# Y-babies_ATtiny84_v03.net
KiCad netlist of a schematic drawn in EAGLE
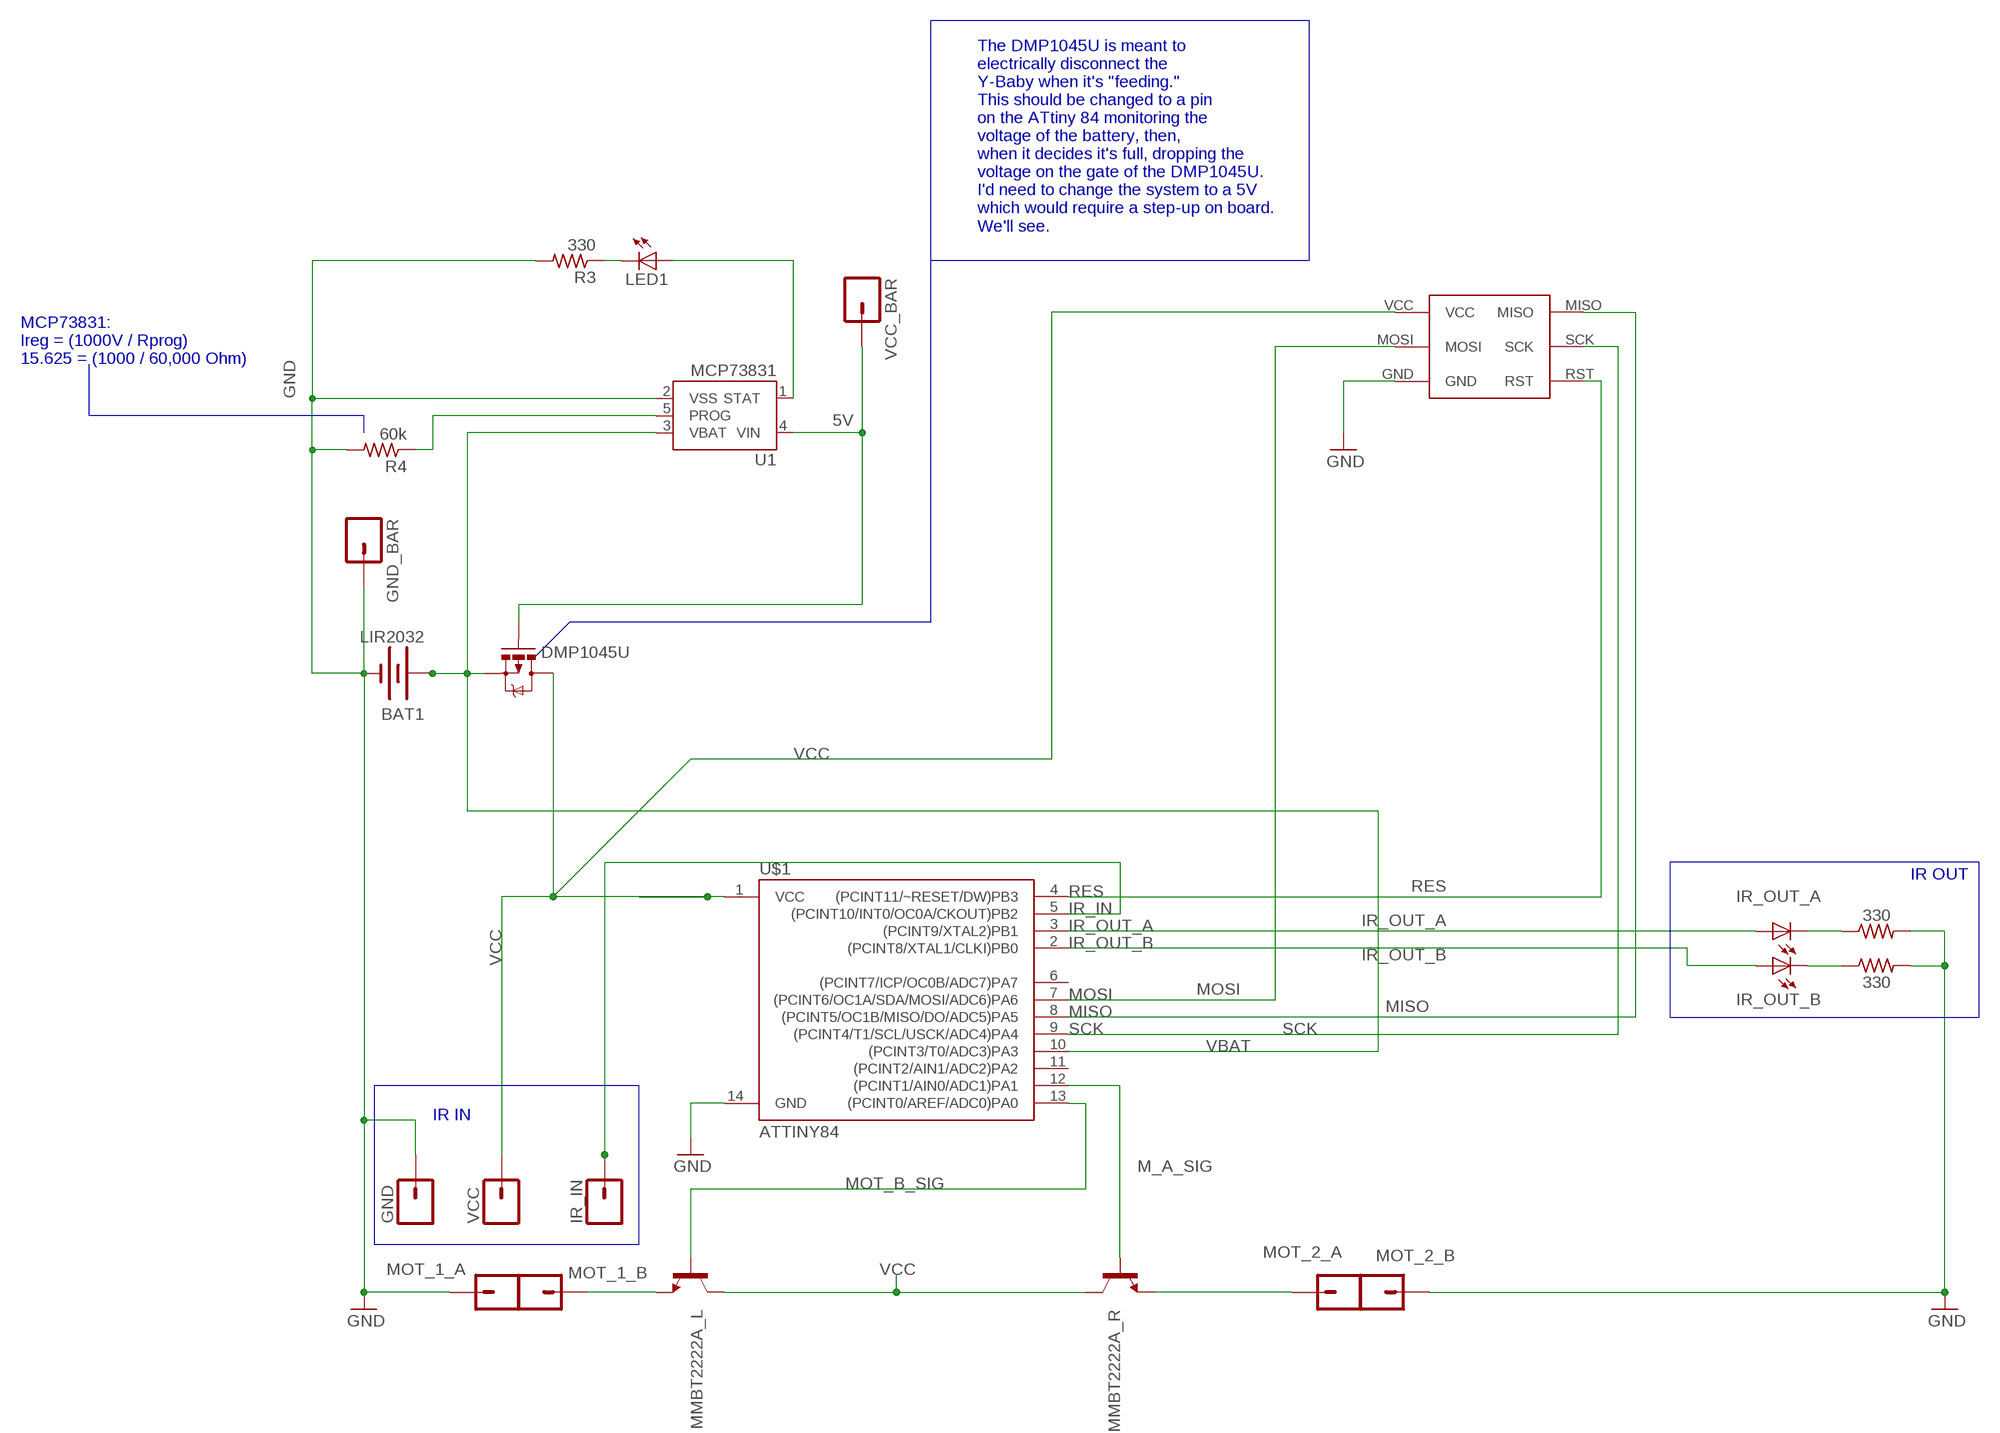
[diagram p0: schematic, sheet 1]

(export (version "E")
  (design (tool "Eeschema 10.0.6"))
  (components
    (comp (ref "BAT1")
      (value "LIR2032")
      (footprint "eagle-import:BATTCOM_20MM_PTH")
      (libsource (lib "eagle-import") (part "BATTERY20PTH"))
    )
    (comp (ref "DMP1045U")
      (value "MOSFET-PCHANNELSMD")
      (footprint "eagle-import:SOT23-3")
      (libsource (lib "eagle-import") (part "MOSFET-PCHANNELSMD"))
    )
    (comp (ref "GND")
      (value "M01PTH")
      (footprint "eagle-import:1X01")
      (libsource (lib "eagle-import") (part "M01PTH"))
    )
    (comp (ref "GND_BAR")
      (value "M01PTH")
      (footprint "eagle-import:1X01")
      (libsource (lib "eagle-import") (part "M01PTH"))
    )
    (comp (ref "IR_IN")
      (value "M01PTH")
      (footprint "eagle-import:1X01")
      (libsource (lib "eagle-import") (part "M01PTH"))
    )
    (comp (ref "IR_OUT_A")
      (value "LED3MM")
      (footprint "eagle-import:LED3MM")
      (libsource (lib "eagle-import") (part "LED3MM"))
    )
    (comp (ref "IR_OUT_B")
      (value "LED3MM")
      (footprint "eagle-import:LED3MM")
      (libsource (lib "eagle-import") (part "LED3MM"))
    )
    (comp (ref "LED1")
      (value "LEDSML0603")
      (footprint "eagle-import:SML0603")
      (libsource (lib "eagle-import") (part "LEDSML0603"))
    )
    (comp (ref "MMBT2222A_L")
      (value "TRANSISTOR_NPNSOT23")
      (footprint "eagle-import:SOT23")
      (libsource (lib "eagle-import") (part "TRANSISTOR_NPNSOT23"))
    )
    (comp (ref "MMBT2222A_R")
      (value "TRANSISTOR_NPNSOT23")
      (footprint "eagle-import:SOT23")
      (libsource (lib "eagle-import") (part "TRANSISTOR_NPNSOT23"))
    )
    (comp (ref "MOT_1_A")
      (value "M01SMD-4.5X1.5")
      (footprint "eagle-import:PAD-1.5X4.5")
      (libsource (lib "eagle-import") (part "M01SMD-4.5X1.5"))
    )
    (comp (ref "MOT_1_B")
      (value "M01SMD-4.5X1.5")
      (footprint "eagle-import:PAD-1.5X4.5")
      (libsource (lib "eagle-import") (part "M01SMD-4.5X1.5"))
    )
    (comp (ref "MOT_2_A")
      (value "M01SMD-4.5X1.5")
      (footprint "eagle-import:PAD-1.5X4.5")
      (libsource (lib "eagle-import") (part "M01SMD-4.5X1.5"))
    )
    (comp (ref "MOT_2_B")
      (value "M01SMD-4.5X1.5")
      (footprint "eagle-import:PAD-1.5X4.5")
      (libsource (lib "eagle-import") (part "M01SMD-4.5X1.5"))
    )
    (comp (ref "R1")
      (value "330")
      (footprint "eagle-import:R0402")
      (libsource (lib "eagle-import") (part "R-US_R0402"))
    )
    (comp (ref "R2")
      (value "330")
      (footprint "eagle-import:R0402")
      (libsource (lib "eagle-import") (part "R-US_R0402"))
    )
    (comp (ref "R3")
      (value "330")
      (footprint "eagle-import:R0402")
      (libsource (lib "eagle-import") (part "R-US_R0402"))
    )
    (comp (ref "R4")
      (value "60k")
      (footprint "eagle-import:R0402")
      (libsource (lib "eagle-import") (part "R-US_R0402"))
    )
    (comp (ref "U$1")
      (value "ATTINY84")
      (footprint "eagle-import:SO14")
      (libsource (lib "eagle-import") (part "ATTINY84"))
    )
    (comp (ref "U$2")
      (value "POGO_PIN_SPI_PAD")
      (footprint "eagle-import:POGO_PIN_SPI_PAD")
      (libsource (lib "eagle-import") (part "POGO_PIN_SPI_PAD"))
    )
    (comp (ref "U1")
      (value "MCP73831")
      (footprint "eagle-import:SOT23-5")
      (libsource (lib "eagle-import") (part "MCP73831"))
    )
    (comp (ref "VCC")
      (value "M01PTH")
      (footprint "eagle-import:1X01")
      (libsource (lib "eagle-import") (part "M01PTH"))
    )
    (comp (ref "VCC_BAR")
      (value "M01PTH")
      (footprint "eagle-import:1X01")
      (libsource (lib "eagle-import") (part "M01PTH"))
    )
  )
  (nets
    (net (code "1") (name "/5V") (class "Default")
      (node (ref "DMP1045U") (pin "1") (pinfunction "G_1") (pintype "passive"))
      (node (ref "U1") (pin "4") (pinfunction "VIN_4") (pintype "power_in"))
      (node (ref "VCC_BAR") (pin "1") (pinfunction "1_1") (pintype "passive"))
    )
    (net (code "2") (name "/IR_IN") (class "Default")
      (node (ref "IR_IN") (pin "1") (pinfunction "1_1") (pintype "passive"))
      (node (ref "U$1") (pin "5") (pinfunction "(PCINT10/INT0/OC0A/CKOUT)PB2_5") (pintype "bidirectional"))
    )
    (net (code "3") (name "/IR_OUT_A") (class "Default")
      (node (ref "IR_OUT_A") (pin "A") (pinfunction "A_A") (pintype "passive"))
      (node (ref "U$1") (pin "3") (pinfunction "(PCINT9/XTAL2)PB1_3") (pintype "bidirectional"))
    )
    (net (code "4") (name "/IR_OUT_B") (class "Default")
      (node (ref "IR_OUT_B") (pin "A") (pinfunction "A_A") (pintype "passive"))
      (node (ref "U$1") (pin "2") (pinfunction "(PCINT8/XTAL1/CLKI)PB0_2") (pintype "bidirectional"))
    )
    (net (code "5") (name "/MISO") (class "Default")
      (node (ref "U$1") (pin "8") (pinfunction "(PCINT5/OC1B/MISO/DO/ADC5)PA5_8") (pintype "bidirectional"))
      (node (ref "U$2") (pin "MISO") (pinfunction "MISO_MISO") (pintype "bidirectional"))
    )
    (net (code "6") (name "/MOSI") (class "Default")
      (node (ref "U$1") (pin "7") (pinfunction "(PCINT6/OC1A/SDA/MOSI/ADC6)PA6_7") (pintype "bidirectional"))
      (node (ref "U$2") (pin "MOSI") (pinfunction "MOSI_MOSI") (pintype "bidirectional"))
    )
    (net (code "7") (name "/MOT_B_SIG") (class "Default")
      (node (ref "MMBT2222A_L") (pin "1") (pinfunction "B_1") (pintype "passive"))
      (node (ref "U$1") (pin "13") (pinfunction "(PCINT0/AREF/ADC0)PA0_13") (pintype "bidirectional"))
    )
    (net (code "8") (name "/M_A_SIG") (class "Default")
      (node (ref "MMBT2222A_R") (pin "1") (pinfunction "B_1") (pintype "passive"))
      (node (ref "U$1") (pin "12") (pinfunction "(PCINT1/AIN0/ADC1)PA1_12") (pintype "bidirectional"))
    )
    (net (code "9") (name "/RES") (class "Default")
      (node (ref "U$1") (pin "4") (pinfunction "(PCINT11/~{RESET/DW})PB3_4") (pintype "bidirectional"))
      (node (ref "U$2") (pin "RST") (pinfunction "RST_RST") (pintype "bidirectional"))
    )
    (net (code "10") (name "/SCK") (class "Default")
      (node (ref "U$1") (pin "9") (pinfunction "(PCINT4/T1/SCL/USCK/ADC4)PA4_9") (pintype "bidirectional"))
      (node (ref "U$2") (pin "SCK") (pinfunction "SCK_SCK") (pintype "bidirectional"))
    )
    (net (code "11") (name "/VBAT") (class "Default")
      (node (ref "BAT1") (pin "1") (pinfunction "+_1") (pintype "power_in"))
      (node (ref "DMP1045U") (pin "2") (pinfunction "S_2") (pintype "passive"))
      (node (ref "U$1") (pin "10") (pinfunction "(PCINT3/T0/ADC3)PA3_10") (pintype "bidirectional"))
      (node (ref "U1") (pin "3") (pinfunction "VBAT_3") (pintype "power_in"))
    )
    (net (code "12") (name "/VCC") (class "Default")
      (node (ref "DMP1045U") (pin "3") (pinfunction "D_3") (pintype "passive"))
      (node (ref "MMBT2222A_L") (pin "3") (pinfunction "C_3") (pintype "passive"))
      (node (ref "MMBT2222A_R") (pin "3") (pinfunction "C_3") (pintype "passive"))
      (node (ref "U$1") (pin "1") (pinfunction "VCC_1") (pintype "bidirectional"))
      (node (ref "U$2") (pin "VCC") (pinfunction "VCC_VCC") (pintype "bidirectional"))
      (node (ref "VCC") (pin "1") (pinfunction "1_1") (pintype "passive"))
    )
    (net (code "13") (name "GND") (class "Default")
      (node (ref "BAT1") (pin "2") (pinfunction "-_2") (pintype "power_in"))
      (node (ref "GND") (pin "1") (pinfunction "1_1") (pintype "passive"))
      (node (ref "GND_BAR") (pin "1") (pinfunction "1_1") (pintype "passive"))
      (node (ref "MOT_1_A") (pin "P$1") (pinfunction "1_P$1") (pintype "passive"))
      (node (ref "MOT_2_B") (pin "P$1") (pinfunction "1_P$1") (pintype "passive"))
      (node (ref "R1") (pin "2") (pinfunction "2_2") (pintype "passive"))
      (node (ref "R2") (pin "2") (pinfunction "2_2") (pintype "passive"))
      (node (ref "R3") (pin "2") (pinfunction "2_2") (pintype "passive"))
      (node (ref "R4") (pin "2") (pinfunction "2_2") (pintype "passive"))
      (node (ref "U$1") (pin "14") (pinfunction "GND_14") (pintype "bidirectional"))
      (node (ref "U$2") (pin "GND") (pinfunction "GND_GND") (pintype "bidirectional"))
      (node (ref "U1") (pin "2") (pinfunction "VSS_2") (pintype "power_in"))
    )
    (net (code "14") (name "Net-(IR_OUT_A-C)") (class "Default")
      (node (ref "IR_OUT_A") (pin "K") (pinfunction "C_K") (pintype "passive"))
      (node (ref "R1") (pin "1") (pinfunction "1_1") (pintype "passive"))
    )
    (net (code "15") (name "Net-(IR_OUT_B-C)") (class "Default")
      (node (ref "IR_OUT_B") (pin "K") (pinfunction "C_K") (pintype "passive"))
      (node (ref "R2") (pin "1") (pinfunction "1_1") (pintype "passive"))
    )
    (net (code "16") (name "Net-(LED1-PadC)") (class "Default")
      (node (ref "LED1") (pin "C") (pinfunction "C_C") (pintype "passive"))
      (node (ref "R3") (pin "1") (pinfunction "1_1") (pintype "passive"))
    )
    (net (code "17") (name "Net-(MMBT2222A_L-E)") (class "Default")
      (node (ref "MMBT2222A_L") (pin "2") (pinfunction "E_2") (pintype "passive"))
      (node (ref "MOT_1_B") (pin "P$1") (pinfunction "1_P$1") (pintype "passive"))
    )
    (net (code "18") (name "Net-(MMBT2222A_R-E)") (class "Default")
      (node (ref "MMBT2222A_R") (pin "2") (pinfunction "E_2") (pintype "passive"))
      (node (ref "MOT_2_A") (pin "P$1") (pinfunction "1_P$1") (pintype "passive"))
    )
    (net (code "19") (name "Net-(U1-PROG)") (class "Default")
      (node (ref "R4") (pin "1") (pinfunction "1_1") (pintype "passive"))
      (node (ref "U1") (pin "5") (pinfunction "PROG_5") (pintype "input"))
    )
    (net (code "20") (name "Net-(U1-STAT)") (class "Default")
      (node (ref "LED1") (pin "A") (pinfunction "A_A") (pintype "passive"))
      (node (ref "U1") (pin "1") (pinfunction "STAT_1") (pintype "output"))
    )
    (net (code "21") (name "unconnected-(U$1-(PCINT2{slash}AIN1{slash}ADC2)PA2-Pad11)") (class "Default")
      (node (ref "U$1") (pin "11") (pinfunction "(PCINT2/AIN1/ADC2)PA2_11") (pintype "bidirectional"))
    )
    (net (code "22") (name "unconnected-(U$1-(PCINT7{slash}ICP{slash}OC0B{slash}ADC7)PA7-Pad6)") (class "Default")
      (node (ref "U$1") (pin "6") (pinfunction "(PCINT7/ICP/OC0B/ADC7)PA7_6") (pintype "bidirectional"))
    )
  )
)
